# Main.net
KiCad netlist of a schematic drawn in Altium Designer
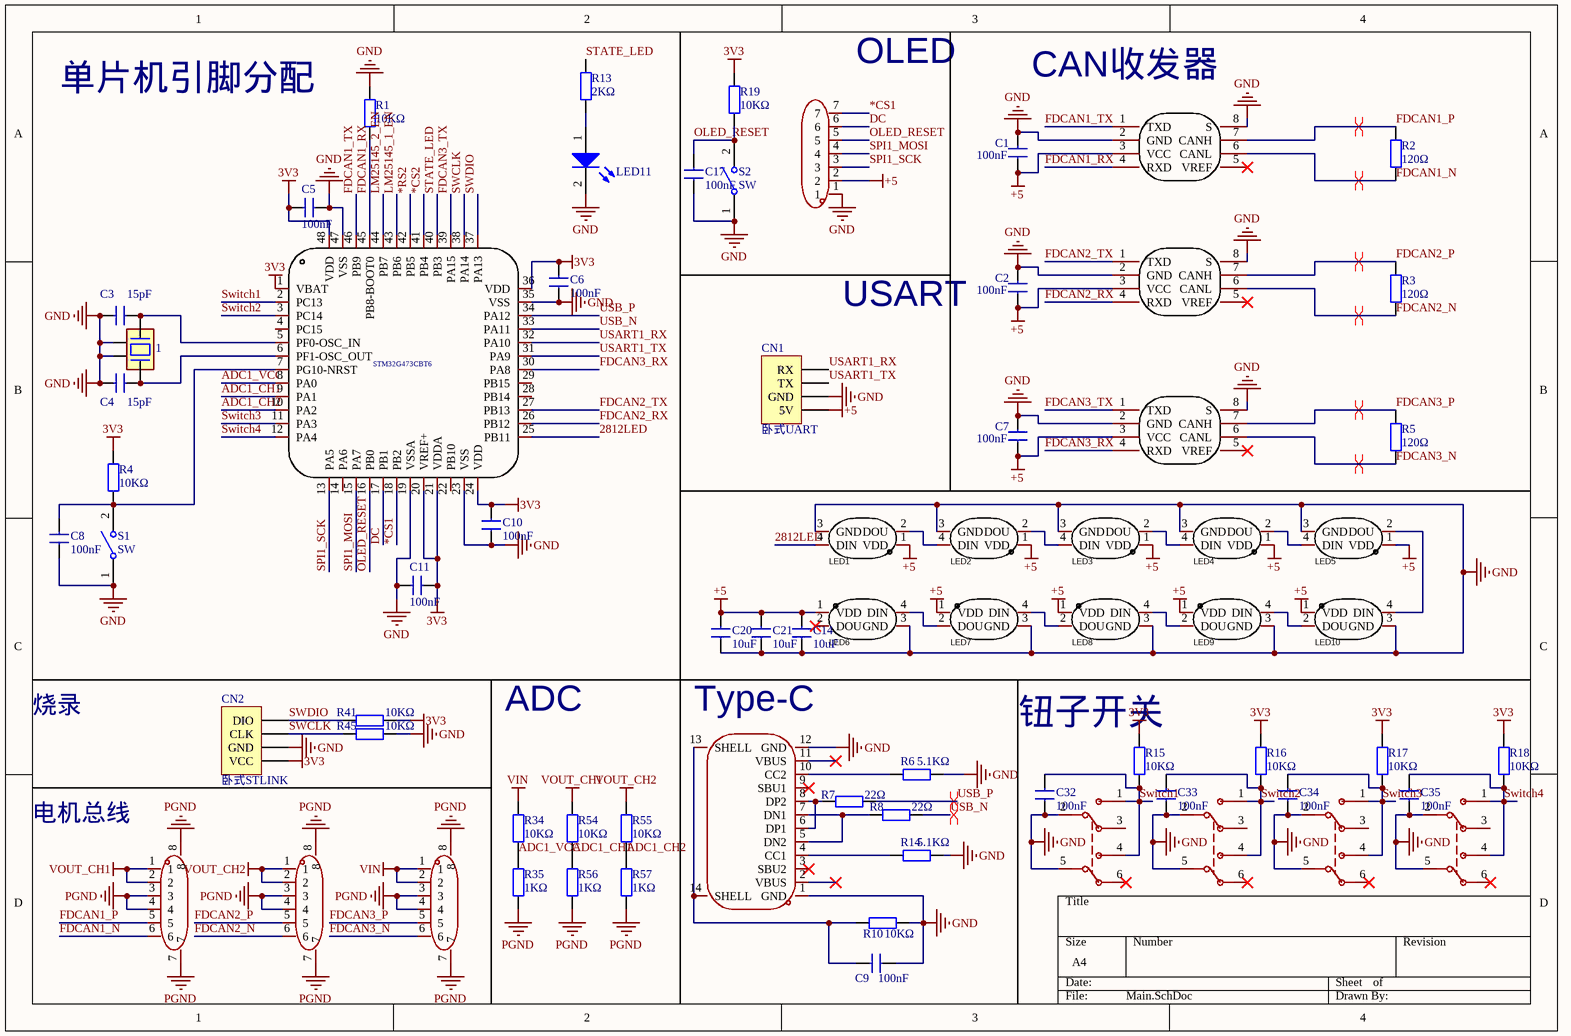
[diagram p0: Main.SchDoc]

(export (version "E")
  (design (tool "Eeschema 10.0.6"))
  (components
    (comp (ref "1")
      (value "3225贴片晶振")
      (footprint "OSC-3225-4P")
      (libsource (lib "Integrated_Library1") (part "3225贴片晶振"))
    )
    (comp (ref "C1")
      (value "100nF")
      (footprint "c0402")
      (description "贴片电容0402")
      (libsource (lib "Integrated_Library1") (part "0402贴片电容"))
    )
    (comp (ref "C2")
      (value "100nF")
      (footprint "c0402")
      (description "贴片电容0402")
      (libsource (lib "Integrated_Library1") (part "0402贴片电容"))
    )
    (comp (ref "C3")
      (value "15pF")
      (footprint "c0402")
      (description "贴片电容0402")
      (libsource (lib "Integrated_Library1") (part "0402贴片电容"))
    )
    (comp (ref "C4")
      (value "15pF")
      (footprint "c0402")
      (description "贴片电容0402")
      (libsource (lib "Integrated_Library1") (part "0402贴片电容"))
    )
    (comp (ref "C5")
      (value "100nF")
      (footprint "c0402")
      (description "贴片电容0402")
      (libsource (lib "Integrated_Library1") (part "0402贴片电容"))
    )
    (comp (ref "C6")
      (value "100nF")
      (footprint "c0402")
      (description "贴片电容0402")
      (libsource (lib "Integrated_Library1") (part "0402贴片电容"))
    )
    (comp (ref "C7")
      (value "100nF")
      (footprint "c0402")
      (description "贴片电容0402")
      (libsource (lib "Integrated_Library1") (part "0402贴片电容"))
    )
    (comp (ref "C8")
      (value "100nF")
      (footprint "c0402")
      (description "贴片电容0402")
      (libsource (lib "Integrated_Library1") (part "0402贴片电容"))
    )
    (comp (ref "C9")
      (value "100nF")
      (footprint "c0402")
      (description "贴片电容0402")
      (libsource (lib "Integrated_Library1") (part "0402贴片电容"))
    )
    (comp (ref "C10")
      (value "100nF")
      (footprint "c0402")
      (description "贴片电容0402")
      (libsource (lib "Integrated_Library1") (part "0402贴片电容"))
    )
    (comp (ref "C11")
      (value "100nF")
      (footprint "c0402")
      (description "贴片电容0402")
      (libsource (lib "Integrated_Library1") (part "0402贴片电容"))
    )
    (comp (ref "C14")
      (value "10uF")
      (footprint "1210")
      (description "1210贴片电容")
      (libsource (lib "Integrated_Library1") (part "1210贴片电容"))
    )
    (comp (ref "C17")
      (value "100nF")
      (footprint "c0402")
      (description "贴片电容0402")
      (libsource (lib "Integrated_Library1") (part "0402贴片电容"))
    )
    (comp (ref "C20")
      (value "10uF")
      (footprint "1210")
      (description "1210贴片电容")
      (libsource (lib "Integrated_Library1") (part "1210贴片电容"))
    )
    (comp (ref "C21")
      (value "10uF")
      (footprint "1210")
      (description "1210贴片电容")
      (libsource (lib "Integrated_Library1") (part "1210贴片电容"))
    )
    (comp (ref "C32")
      (value "100nF")
      (footprint "c0402")
      (description "贴片电容0402")
      (libsource (lib "Integrated_Library1") (part "0402贴片电容"))
    )
    (comp (ref "C33")
      (value "100nF")
      (footprint "c0402")
      (description "贴片电容0402")
      (libsource (lib "Integrated_Library1") (part "0402贴片电容"))
    )
    (comp (ref "C34")
      (value "100nF")
      (footprint "c0402")
      (description "贴片电容0402")
      (libsource (lib "Integrated_Library1") (part "0402贴片电容"))
    )
    (comp (ref "C35")
      (value "100nF")
      (footprint "c0402")
      (description "贴片电容0402")
      (libsource (lib "Integrated_Library1") (part "0402贴片电容"))
    )
    (comp (ref "CN1")
      (value "卧式UART")
      (footprint "CONN-SMD_4P-P1.25_GH1.25-4P")
      (libsource (lib "Integrated_Library1") (part "卧式UART"))
    )
    (comp (ref "CN2")
      (value "卧式STLINK")
      (footprint "CONN-SMD_4P-P1.25_GH1.25-4P")
      (libsource (lib "Integrated_Library1") (part "卧式STLINK"))
    )
    (comp (ref "H1")
      (value "PM254V-11-07-H85")
      (footprint "HDR-TH_7P-P2.54-V-F")
      (fields (field (name "MANUFACTURER") "XFCN(兴飞)"))
      (libsource (lib "Schlib1") (part "PM254V-11-07-H85"))
    )
    (comp (ref "LED1")
      (value "XL-5050RGBC-WS2812B")
      (footprint "LED-SMD_4P-L5.0-W5.0-BL_XL-5050RGBC")
      (description "WS2812B彩灯珠")
      (fields (field (name "MANUFACTURER") "XINGLIGHT(成兴光)"))
      (libsource (lib "RoBoMaster_AllComponent") (part "WS2812B彩灯珠"))
    )
    (comp (ref "LED2")
      (value "XL-5050RGBC-WS2812B")
      (footprint "LED-SMD_4P-L5.0-W5.0-BL_XL-5050RGBC")
      (description "WS2812B彩灯珠")
      (fields (field (name "MANUFACTURER") "XINGLIGHT(成兴光)"))
      (libsource (lib "RoBoMaster_AllComponent") (part "WS2812B彩灯珠"))
    )
    (comp (ref "LED3")
      (value "XL-5050RGBC-WS2812B")
      (footprint "LED-SMD_4P-L5.0-W5.0-BL_XL-5050RGBC")
      (description "WS2812B彩灯珠")
      (fields (field (name "MANUFACTURER") "XINGLIGHT(成兴光)"))
      (libsource (lib "RoBoMaster_AllComponent") (part "WS2812B彩灯珠"))
    )
    (comp (ref "LED4")
      (value "XL-5050RGBC-WS2812B")
      (footprint "LED-SMD_4P-L5.0-W5.0-BL_XL-5050RGBC")
      (description "WS2812B彩灯珠")
      (fields (field (name "MANUFACTURER") "XINGLIGHT(成兴光)"))
      (libsource (lib "RoBoMaster_AllComponent") (part "WS2812B彩灯珠"))
    )
    (comp (ref "LED5")
      (value "XL-5050RGBC-WS2812B")
      (footprint "LED-SMD_4P-L5.0-W5.0-BL_XL-5050RGBC")
      (description "WS2812B彩灯珠")
      (fields (field (name "MANUFACTURER") "XINGLIGHT(成兴光)"))
      (libsource (lib "RoBoMaster_AllComponent") (part "WS2812B彩灯珠"))
    )
    (comp (ref "LED6")
      (value "XL-5050RGBC-WS2812B")
      (footprint "LED-SMD_4P-L5.0-W5.0-BL_XL-5050RGBC")
      (description "WS2812B彩灯珠")
      (fields (field (name "MANUFACTURER") "XINGLIGHT(成兴光)"))
      (libsource (lib "RoBoMaster_AllComponent") (part "WS2812B彩灯珠"))
    )
    (comp (ref "LED7")
      (value "XL-5050RGBC-WS2812B")
      (footprint "LED-SMD_4P-L5.0-W5.0-BL_XL-5050RGBC")
      (description "WS2812B彩灯珠")
      (fields (field (name "MANUFACTURER") "XINGLIGHT(成兴光)"))
      (libsource (lib "RoBoMaster_AllComponent") (part "WS2812B彩灯珠"))
    )
    (comp (ref "LED8")
      (value "XL-5050RGBC-WS2812B")
      (footprint "LED-SMD_4P-L5.0-W5.0-BL_XL-5050RGBC")
      (description "WS2812B彩灯珠")
      (fields (field (name "MANUFACTURER") "XINGLIGHT(成兴光)"))
      (libsource (lib "RoBoMaster_AllComponent") (part "WS2812B彩灯珠"))
    )
    (comp (ref "LED9")
      (value "XL-5050RGBC-WS2812B")
      (footprint "LED-SMD_4P-L5.0-W5.0-BL_XL-5050RGBC")
      (description "WS2812B彩灯珠")
      (fields (field (name "MANUFACTURER") "XINGLIGHT(成兴光)"))
      (libsource (lib "RoBoMaster_AllComponent") (part "WS2812B彩灯珠"))
    )
    (comp (ref "LED10")
      (value "XL-5050RGBC-WS2812B")
      (footprint "LED-SMD_4P-L5.0-W5.0-BL_XL-5050RGBC")
      (description "WS2812B彩灯珠")
      (fields (field (name "MANUFACTURER") "XINGLIGHT(成兴光)"))
      (libsource (lib "RoBoMaster_AllComponent") (part "WS2812B彩灯珠"))
    )
    (comp (ref "LED11")
      (value "LED")
      (footprint "led0805")
      (description "0805贴片LED")
      (libsource (lib "Integrated_Library1") (part "0805贴片LED"))
    )
    (comp (ref "R1")
      (value "10KΩ")
      (footprint "R0402")
      (description "0402贴片电阻")
      (libsource (lib "") (part "0402贴片电阻_4"))
    )
    (comp (ref "R2")
      (value "120Ω")
      (footprint "R0402")
      (description "0402贴片电阻")
      (libsource (lib "Integrated_Library1") (part "0402贴片电阻"))
    )
    (comp (ref "R3")
      (value "120Ω")
      (footprint "R0402")
      (description "0402贴片电阻")
      (libsource (lib "Integrated_Library1") (part "0402贴片电阻"))
    )
    (comp (ref "R4")
      (value "10KΩ")
      (footprint "R0402")
      (description "0402贴片电阻")
      (libsource (lib "Integrated_Library1") (part "0402贴片电阻"))
    )
    (comp (ref "R5")
      (value "120Ω")
      (footprint "R0402")
      (description "0402贴片电阻")
      (libsource (lib "Integrated_Library1") (part "0402贴片电阻"))
    )
    (comp (ref "R6")
      (value "5.1KΩ")
      (footprint "R0402")
      (description "0402贴片电阻")
      (libsource (lib "") (part "0402贴片电阻_1"))
    )
    (comp (ref "R7")
      (value "22Ω")
      (footprint "R0402")
      (description "0402贴片电阻")
      (libsource (lib "") (part "0402贴片电阻_1"))
    )
    (comp (ref "R8")
      (value "22Ω")
      (footprint "R0402")
      (description "0402贴片电阻")
      (libsource (lib "") (part "0402贴片电阻_1"))
    )
    (comp (ref "R10")
      (value "10KΩ")
      (footprint "R0402")
      (description "0402贴片电阻")
      (libsource (lib "") (part "0402贴片电阻_1"))
    )
    (comp (ref "R13")
      (value "2KΩ")
      (footprint "R0402")
      (description "0402贴片电阻")
      (libsource (lib "") (part "0402贴片电阻_3"))
    )
    (comp (ref "R14")
      (value "5.1KΩ")
      (footprint "R0402")
      (description "0402贴片电阻")
      (libsource (lib "") (part "0402贴片电阻_1"))
    )
    (comp (ref "R15")
      (value "10KΩ")
      (footprint "R0402")
      (description "0402贴片电阻")
      (libsource (lib "Integrated_Library1") (part "0402贴片电阻"))
    )
    (comp (ref "R16")
      (value "10KΩ")
      (footprint "R0402")
      (description "0402贴片电阻")
      (libsource (lib "Integrated_Library1") (part "0402贴片电阻"))
    )
    (comp (ref "R17")
      (value "10KΩ")
      (footprint "R0402")
      (description "0402贴片电阻")
      (libsource (lib "Integrated_Library1") (part "0402贴片电阻"))
    )
    (comp (ref "R18")
      (value "10KΩ")
      (footprint "R0402")
      (description "0402贴片电阻")
      (libsource (lib "Integrated_Library1") (part "0402贴片电阻"))
    )
    (comp (ref "R19")
      (value "10KΩ")
      (footprint "R0402")
      (description "0402贴片电阻")
      (libsource (lib "Integrated_Library1") (part "0402贴片电阻"))
    )
    (comp (ref "R34")
      (value "10KΩ")
      (footprint "R0402")
      (description "0402贴片电阻")
      (libsource (lib "") (part "0402贴片电阻_2"))
    )
    (comp (ref "R35")
      (value "1KΩ")
      (footprint "R0402")
      (description "0402贴片电阻")
      (libsource (lib "") (part "0402贴片电阻_2"))
    )
    (comp (ref "R41")
      (value "10KΩ")
      (footprint "R0402")
      (description "0402贴片电阻")
      (libsource (lib "") (part "0402贴片电阻_1"))
    )
    (comp (ref "R45")
      (value "10KΩ")
      (footprint "R0402")
      (description "0402贴片电阻")
      (libsource (lib "") (part "0402贴片电阻_1"))
    )
    (comp (ref "R54")
      (value "10KΩ")
      (footprint "R0402")
      (description "0402贴片电阻")
      (libsource (lib "") (part "0402贴片电阻_2"))
    )
    (comp (ref "R55")
      (value "10KΩ")
      (footprint "R0402")
      (description "0402贴片电阻")
      (libsource (lib "") (part "0402贴片电阻_2"))
    )
    (comp (ref "R56")
      (value "1KΩ")
      (footprint "R0402")
      (description "0402贴片电阻")
      (libsource (lib "") (part "0402贴片电阻_2"))
    )
    (comp (ref "R57")
      (value "1KΩ")
      (footprint "R0402")
      (description "0402贴片电阻")
      (libsource (lib "") (part "0402贴片电阻_2"))
    )
    (comp (ref "S1")
      (value "SW")
      (footprint "KEY_SMD")
      (description "开关")
      (libsource (lib "Integrated_Library1") (part "SW"))
    )
    (comp (ref "S2")
      (value "SW")
      (footprint "KEY_SMD")
      (description "开关")
      (libsource (lib "Integrated_Library1") (part "SW"))
    )
    (comp (ref "U1")
      (value "ZX-ZH1.5-6PWT")
      (footprint "CONN-SMD_6P-P1.50_ZX-ZH1.5-6PWT")
      (fields (field (name "MANUFACTURER") "Megastar(兆星)"))
      (libsource (lib "Schlib1") (part "ZX-ZH1.5-6PWT"))
    )
    (comp (ref "U2")
      (value "SN65HVD1050DR")
      (footprint "SOIC-8_L4.9-W3.9-P1.27-LS6.0-BL")
      (description "CAN芯片")
      (fields (field (name "MANUFACTURER") "TI(德州仪器)"))
      (libsource (lib "Integrated_Library1") (part "SN65HVD1050DR"))
    )
    (comp (ref "U3")
      (value "ZX-ZH1.5-6PWT")
      (footprint "CONN-SMD_6P-P1.50_ZX-ZH1.5-6PWT")
      (fields (field (name "MANUFACTURER") "Megastar(兆星)"))
      (libsource (lib "Schlib1") (part "ZX-ZH1.5-6PWT"))
    )
    (comp (ref "U4")
      (value "STM32G474CET6")
      (footprint "LQFP-48")
      (fields (field (name "MANUFACTURER") "ST(意法半导体)") (field (name "MANUFACTURER PART") "STM32G473CBT6"))
      (libsource (lib "Integrated_Library1") (part "STM32G474CET6"))
    )
    (comp (ref "U5")
      (value "SN65HVD1050DR")
      (footprint "SOIC-8_L4.9-W3.9-P1.27-LS6.0-BL")
      (description "CAN芯片")
      (fields (field (name "MANUFACTURER") "TI(德州仪器)"))
      (libsource (lib "Integrated_Library1") (part "SN65HVD1050DR"))
    )
    (comp (ref "U6")
      (value "ZX-ZH1.5-6PWT")
      (footprint "CONN-SMD_6P-P1.50_ZX-ZH1.5-6PWT")
      (fields (field (name "MANUFACTURER") "Megastar(兆星)"))
      (libsource (lib "Schlib1") (part "ZX-ZH1.5-6PWT"))
    )
    (comp (ref "U8")
      (value "SN65HVD1050DR")
      (footprint "SOIC-8_L4.9-W3.9-P1.27-LS6.0-BL")
      (description "CAN芯片")
      (fields (field (name "MANUFACTURER") "TI(德州仪器)"))
      (libsource (lib "Integrated_Library1") (part "SN65HVD1050DR"))
    )
    (comp (ref "U9")
      (value "7208P1YZQI")
      (footprint "SW-TH_6P-L12.7-W11.4-P4.70-LS4.8")
      (fields (field (name "MANUFACTURER") "C&K"))
      (libsource (lib "Schlib1") (part "7208P1YZQI"))
    )
    (comp (ref "U10")
      (value "7208P1YZQI")
      (footprint "SW-TH_6P-L12.7-W11.4-P4.70-LS4.8")
      (fields (field (name "MANUFACTURER") "C&K"))
      (libsource (lib "Schlib1") (part "7208P1YZQI"))
    )
    (comp (ref "U11")
      (value "7208P1YZQI")
      (footprint "SW-TH_6P-L12.7-W11.4-P4.70-LS4.8")
      (fields (field (name "MANUFACTURER") "C&K"))
      (libsource (lib "Schlib1") (part "7208P1YZQI"))
    )
    (comp (ref "U12")
      (value "7208P1YZQI")
      (footprint "SW-TH_6P-L12.7-W11.4-P4.70-LS4.8")
      (fields (field (name "MANUFACTURER") "C&K"))
      (libsource (lib "Schlib1") (part "7208P1YZQI"))
    )
    (comp (ref "USB1")
      (value "TYPE-C 16PIN 2MD(073)")
      (footprint "USB-C-SMD_TYPE-C-6PIN-2MD-073")
      (fields (field (name "MANUFACTURER") "SHOU HAN(首韩)"))
      (libsource (lib "Schlib1") (part "TYPE-C 16PIN 2MD(073)"))
    )
  )
  (nets
    (net (code "1") (name "+5") (class "Default")
      (node (ref "C1") (pin "1") (pinfunction "1_1") (pintype "passive"))
      (node (ref "C14") (pin "2") (pinfunction "2_2") (pintype "passive"))
      (node (ref "C2") (pin "1") (pinfunction "1_1") (pintype "passive"))
      (node (ref "C20") (pin "2") (pinfunction "2_2") (pintype "passive"))
      (node (ref "C21") (pin "2") (pinfunction "2_2") (pintype "passive"))
      (node (ref "C7") (pin "1") (pinfunction "1_1") (pintype "passive"))
      (node (ref "CN1") (pin "1") (pinfunction "5V_1") (pintype "passive"))
      (node (ref "H1") (pin "2") (pinfunction "2_2") (pintype "passive"))
      (node (ref "LED1") (pin "1") (pinfunction "VDD_1") (pintype "passive"))
      (node (ref "LED10") (pin "1") (pinfunction "VDD_1") (pintype "passive"))
      (node (ref "LED2") (pin "1") (pinfunction "VDD_1") (pintype "passive"))
      (node (ref "LED3") (pin "1") (pinfunction "VDD_1") (pintype "passive"))
      (node (ref "LED4") (pin "1") (pinfunction "VDD_1") (pintype "passive"))
      (node (ref "LED5") (pin "1") (pinfunction "VDD_1") (pintype "passive"))
      (node (ref "LED6") (pin "1") (pinfunction "VDD_1") (pintype "passive"))
      (node (ref "LED7") (pin "1") (pinfunction "VDD_1") (pintype "passive"))
      (node (ref "LED8") (pin "1") (pinfunction "VDD_1") (pintype "passive"))
      (node (ref "LED9") (pin "1") (pinfunction "VDD_1") (pintype "passive"))
      (node (ref "U2") (pin "3") (pinfunction "VCC_3") (pintype "passive"))
      (node (ref "U5") (pin "3") (pinfunction "VCC_3") (pintype "passive"))
      (node (ref "U8") (pin "3") (pinfunction "VCC_3") (pintype "passive"))
    )
    (net (code "2") (name "/*CS1") (class "Default")
      (node (ref "H1") (pin "7") (pinfunction "7_7") (pintype "passive"))
      (node (ref "U4") (pin "18") (pinfunction "PB2_18") (pintype "passive"))
    )
    (net (code "3") (name "/*CS2") (class "Default")
      (node (ref "U4") (pin "41") (pinfunction "PB4_41") (pintype "passive"))
    )
    (net (code "4") (name "/*RS2") (class "Default")
      (node (ref "U4") (pin "42") (pinfunction "PB5_42") (pintype "passive"))
    )
    (net (code "5") (name "/2812LED") (class "Default")
      (node (ref "LED1") (pin "4") (pinfunction "DIN_4") (pintype "passive"))
      (node (ref "U4") (pin "25") (pinfunction "PB11_25") (pintype "passive"))
    )
    (net (code "6") (name "/ADC1_CH1") (class "Default")
      (node (ref "R54") (pin "1") (pinfunction "1_1") (pintype "passive"))
      (node (ref "R56") (pin "2") (pinfunction "2_2") (pintype "passive"))
      (node (ref "U4") (pin "9") (pinfunction "PA1_9") (pintype "passive"))
    )
    (net (code "7") (name "/ADC1_CH2") (class "Default")
      (node (ref "R55") (pin "1") (pinfunction "1_1") (pintype "passive"))
      (node (ref "R57") (pin "2") (pinfunction "2_2") (pintype "passive"))
      (node (ref "U4") (pin "10") (pinfunction "PA2_10") (pintype "passive"))
    )
    (net (code "8") (name "/ADC1_VCC") (class "Default")
      (node (ref "R34") (pin "1") (pinfunction "1_1") (pintype "passive"))
      (node (ref "R35") (pin "2") (pinfunction "2_2") (pintype "passive"))
      (node (ref "U4") (pin "8") (pinfunction "PA0_8") (pintype "passive"))
    )
    (net (code "9") (name "/DC") (class "Default")
      (node (ref "H1") (pin "6") (pinfunction "6_6") (pintype "passive"))
      (node (ref "U4") (pin "17") (pinfunction "PB1_17") (pintype "passive"))
    )
    (net (code "10") (name "/FDCAN1_N") (class "Default")
      (node (ref "R2") (pin "1") (pinfunction "1_1") (pintype "passive"))
      (node (ref "U1") (pin "6") (pinfunction "6_6") (pintype "passive"))
      (node (ref "U2") (pin "6") (pinfunction "CANL_6") (pintype "passive"))
    )
    (net (code "11") (name "/FDCAN1_P") (class "Default")
      (node (ref "R2") (pin "2") (pinfunction "2_2") (pintype "passive"))
      (node (ref "U1") (pin "5") (pinfunction "5_5") (pintype "passive"))
      (node (ref "U2") (pin "7") (pinfunction "CANH_7") (pintype "passive"))
    )
    (net (code "12") (name "/FDCAN1_RX") (class "Default")
      (node (ref "R1") (pin "2") (pinfunction "2_2") (pintype "passive"))
      (node (ref "U2") (pin "4") (pinfunction "RXD_4") (pintype "passive"))
      (node (ref "U4") (pin "45") (pinfunction "PB8-BOOT0_45") (pintype "passive"))
    )
    (net (code "13") (name "/FDCAN1_TX") (class "Default")
      (node (ref "U2") (pin "1") (pinfunction "TXD_1") (pintype "passive"))
      (node (ref "U4") (pin "46") (pinfunction "PB9_46") (pintype "passive"))
    )
    (net (code "14") (name "/FDCAN2_N") (class "Default")
      (node (ref "R3") (pin "1") (pinfunction "1_1") (pintype "passive"))
      (node (ref "U3") (pin "6") (pinfunction "6_6") (pintype "passive"))
      (node (ref "U5") (pin "6") (pinfunction "CANL_6") (pintype "passive"))
    )
    (net (code "15") (name "/FDCAN2_P") (class "Default")
      (node (ref "R3") (pin "2") (pinfunction "2_2") (pintype "passive"))
      (node (ref "U3") (pin "5") (pinfunction "5_5") (pintype "passive"))
      (node (ref "U5") (pin "7") (pinfunction "CANH_7") (pintype "passive"))
    )
    (net (code "16") (name "/FDCAN2_RX") (class "Default")
      (node (ref "U4") (pin "26") (pinfunction "PB12_26") (pintype "passive"))
      (node (ref "U5") (pin "4") (pinfunction "RXD_4") (pintype "passive"))
    )
    (net (code "17") (name "/FDCAN2_TX") (class "Default")
      (node (ref "U4") (pin "27") (pinfunction "PB13_27") (pintype "passive"))
      (node (ref "U5") (pin "1") (pinfunction "TXD_1") (pintype "passive"))
    )
    (net (code "18") (name "/FDCAN3_N") (class "Default")
      (node (ref "R5") (pin "1") (pinfunction "1_1") (pintype "passive"))
      (node (ref "U6") (pin "6") (pinfunction "6_6") (pintype "passive"))
      (node (ref "U8") (pin "6") (pinfunction "CANL_6") (pintype "passive"))
    )
    (net (code "19") (name "/FDCAN3_P") (class "Default")
      (node (ref "R5") (pin "2") (pinfunction "2_2") (pintype "passive"))
      (node (ref "U6") (pin "5") (pinfunction "5_5") (pintype "passive"))
      (node (ref "U8") (pin "7") (pinfunction "CANH_7") (pintype "passive"))
    )
    (net (code "20") (name "/FDCAN3_RX") (class "Default")
      (node (ref "U4") (pin "30") (pinfunction "PA8_30") (pintype "passive"))
      (node (ref "U8") (pin "4") (pinfunction "RXD_4") (pintype "passive"))
    )
    (net (code "21") (name "/FDCAN3_TX") (class "Default")
      (node (ref "U4") (pin "39") (pinfunction "PA15_39") (pintype "passive"))
      (node (ref "U8") (pin "1") (pinfunction "TXD_1") (pintype "passive"))
    )
    (net (code "22") (name "/LM25145_1_EN") (class "Default")
      (node (ref "U4") (pin "43") (pinfunction "PB6_43") (pintype "passive"))
    )
    (net (code "23") (name "/LM25145_2_EN") (class "Default")
      (node (ref "U4") (pin "44") (pinfunction "PB7_44") (pintype "passive"))
    )
    (net (code "24") (name "/OLED_RESET") (class "Default")
      (node (ref "C17") (pin "2") (pinfunction "2_2") (pintype "passive"))
      (node (ref "H1") (pin "5") (pinfunction "5_5") (pintype "passive"))
      (node (ref "R19") (pin "1") (pinfunction "1_1") (pintype "passive"))
      (node (ref "S2") (pin "2") (pinfunction "NO_2") (pintype "passive"))
      (node (ref "U4") (pin "16") (pinfunction "PB0_16") (pintype "passive"))
    )
    (net (code "25") (name "/SPI1_MOSI") (class "Default")
      (node (ref "H1") (pin "4") (pinfunction "4_4") (pintype "passive"))
      (node (ref "U4") (pin "15") (pinfunction "PA7_15") (pintype "passive"))
    )
    (net (code "26") (name "/SPI1_SCK") (class "Default")
      (node (ref "H1") (pin "3") (pinfunction "3_3") (pintype "passive"))
      (node (ref "U4") (pin "13") (pinfunction "PA5_13") (pintype "passive"))
    )
    (net (code "27") (name "/STATE_LED") (class "Default")
      (node (ref "R13") (pin "1") (pinfunction "1_1") (pintype "passive"))
      (node (ref "U4") (pin "40") (pinfunction "PB3_40") (pintype "passive"))
    )
    (net (code "28") (name "/SWCLK") (class "Default")
      (node (ref "CN2") (pin "3") (pinfunction "CLK_3") (pintype "passive"))
      (node (ref "R45") (pin "1") (pinfunction "1_1") (pintype "passive"))
      (node (ref "U4") (pin "38") (pinfunction "PA14_38") (pintype "passive"))
    )
    (net (code "29") (name "/SWDIO") (class "Default")
      (node (ref "CN2") (pin "4") (pinfunction "DIO_4") (pintype "passive"))
      (node (ref "R41") (pin "1") (pinfunction "1_1") (pintype "passive"))
      (node (ref "U4") (pin "37") (pinfunction "PA13_37") (pintype "passive"))
    )
    (net (code "30") (name "/Switch1") (class "Default")
      (node (ref "C32") (pin "2") (pinfunction "2_2") (pintype "passive"))
      (node (ref "R15") (pin "1") (pinfunction "1_1") (pintype "passive"))
      (node (ref "U4") (pin "2") (pinfunction "PC13_2") (pintype "passive"))
      (node (ref "U9") (pin "1") (pinfunction "1_1") (pintype "passive"))
      (node (ref "U9") (pin "4") (pinfunction "4_4") (pintype "passive"))
    )
    (net (code "31") (name "/Switch2") (class "Default")
      (node (ref "C33") (pin "2") (pinfunction "2_2") (pintype "passive"))
      (node (ref "R16") (pin "1") (pinfunction "1_1") (pintype "passive"))
      (node (ref "U10") (pin "1") (pinfunction "1_1") (pintype "passive"))
      (node (ref "U10") (pin "4") (pinfunction "4_4") (pintype "passive"))
      (node (ref "U4") (pin "3") (pinfunction "PC14_3") (pintype "passive"))
    )
    (net (code "32") (name "/Switch3") (class "Default")
      (node (ref "C34") (pin "2") (pinfunction "2_2") (pintype "passive"))
      (node (ref "R17") (pin "1") (pinfunction "1_1") (pintype "passive"))
      (node (ref "U11") (pin "1") (pinfunction "1_1") (pintype "passive"))
      (node (ref "U11") (pin "4") (pinfunction "4_4") (pintype "passive"))
      (node (ref "U4") (pin "11") (pinfunction "PA3_11") (pintype "passive"))
    )
    (net (code "33") (name "/Switch4") (class "Default")
      (node (ref "C35") (pin "2") (pinfunction "2_2") (pintype "passive"))
      (node (ref "R18") (pin "1") (pinfunction "1_1") (pintype "passive"))
      (node (ref "U12") (pin "1") (pinfunction "1_1") (pintype "passive"))
      (node (ref "U12") (pin "4") (pinfunction "4_4") (pintype "passive"))
      (node (ref "U4") (pin "12") (pinfunction "PA4_12") (pintype "passive"))
    )
    (net (code "34") (name "/USART1_RX") (class "Default")
      (node (ref "CN1") (pin "4") (pinfunction "RX_4") (pintype "passive"))
      (node (ref "U4") (pin "32") (pinfunction "PA10_32") (pintype "passive"))
    )
    (net (code "35") (name "/USART1_TX") (class "Default")
      (node (ref "CN1") (pin "3") (pinfunction "TX_3") (pintype "passive"))
      (node (ref "U4") (pin "31") (pinfunction "PA9_31") (pintype "passive"))
    )
    (net (code "36") (name "/USB_N") (class "Default")
      (node (ref "R8") (pin "2") (pinfunction "2_2") (pintype "passive"))
      (node (ref "U4") (pin "33") (pinfunction "PA11_33") (pintype "passive"))
    )
    (net (code "37") (name "/USB_P") (class "Default")
      (node (ref "R7") (pin "2") (pinfunction "2_2") (pintype "passive"))
      (node (ref "U4") (pin "34") (pinfunction "PA12_34") (pintype "passive"))
    )
    (net (code "38") (name "3V3") (class "Default")
      (node (ref "C10") (pin "2") (pinfunction "2_2") (pintype "passive"))
      (node (ref "C11") (pin "1") (pinfunction "1_1") (pintype "passive"))
      (node (ref "C5") (pin "2") (pinfunction "2_2") (pintype "passive"))
      (node (ref "C6") (pin "2") (pinfunction "2_2") (pintype "passive"))
      (node (ref "CN2") (pin "1") (pinfunction "VCC_1") (pintype "passive"))
      (node (ref "R15") (pin "2") (pinfunction "2_2") (pintype "passive"))
      (node (ref "R16") (pin "2") (pinfunction "2_2") (pintype "passive"))
      (node (ref "R17") (pin "2") (pinfunction "2_2") (pintype "passive"))
      (node (ref "R18") (pin "2") (pinfunction "2_2") (pintype "passive"))
      (node (ref "R19") (pin "2") (pinfunction "2_2") (pintype "passive"))
      (node (ref "R4") (pin "2") (pinfunction "2_2") (pintype "passive"))
      (node (ref "R41") (pin "2") (pinfunction "2_2") (pintype "passive"))
      (node (ref "U4") (pin "1") (pinfunction "VBAT_1") (pintype "passive"))
      (node (ref "U4") (pin "20") (pinfunction "VREF+_20") (pintype "passive"))
      (node (ref "U4") (pin "21") (pinfunction "VDDA_21") (pintype "passive"))
      (node (ref "U4") (pin "24") (pinfunction "VDD_24") (pintype "passive"))
      (node (ref "U4") (pin "36") (pinfunction "VDD_36") (pintype "passive"))
      (node (ref "U4") (pin "48") (pinfunction "VDD_48") (pintype "passive"))
    )
    (net (code "39") (name "GND") (class "Default")
      (node (ref "1") (pin "2") (pinfunction "2_2") (pintype "passive"))
      (node (ref "1") (pin "4") (pinfunction "4_4") (pintype "passive"))
      (node (ref "C1") (pin "2") (pinfunction "2_2") (pintype "passive"))
      (node (ref "C10") (pin "1") (pinfunction "1_1") (pintype "passive"))
      (node (ref "C11") (pin "2") (pinfunction "2_2") (pintype "passive"))
      (node (ref "C14") (pin "1") (pinfunction "1_1") (pintype "passive"))
      (node (ref "C17") (pin "1") (pinfunction "1_1") (pintype "passive"))
      (node (ref "C2") (pin "2") (pinfunction "2_2") (pintype "passive"))
      (node (ref "C20") (pin "1") (pinfunction "1_1") (pintype "passive"))
      (node (ref "C21") (pin "1") (pinfunction "1_1") (pintype "passive"))
      (node (ref "C3") (pin "1") (pinfunction "1_1") (pintype "passive"))
      (node (ref "C32") (pin "1") (pinfunction "1_1") (pintype "passive"))
      (node (ref "C33") (pin "1") (pinfunction "1_1") (pintype "passive"))
      (node (ref "C34") (pin "1") (pinfunction "1_1") (pintype "passive"))
      (node (ref "C35") (pin "1") (pinfunction "1_1") (pintype "passive"))
      (node (ref "C4") (pin "1") (pinfunction "1_1") (pintype "passive"))
      (node (ref "C5") (pin "1") (pinfunction "1_1") (pintype "passive"))
      (node (ref "C6") (pin "1") (pinfunction "1_1") (pintype "passive"))
      (node (ref "C7") (pin "2") (pinfunction "2_2") (pintype "passive"))
      (node (ref "C8") (pin "1") (pinfunction "1_1") (pintype "passive"))
      (node (ref "C9") (pin "2") (pinfunction "2_2") (pintype "passive"))
      (node (ref "CN1") (pin "2") (pinfunction "GND_2") (pintype "passive"))
      (node (ref "CN2") (pin "2") (pinfunction "GND_2") (pintype "passive"))
      (node (ref "H1") (pin "1") (pinfunction "1_1") (pintype "passive"))
      (node (ref "LED1") (pin "3") (pinfunction "GND_3") (pintype "passive"))
      (node (ref "LED10") (pin "3") (pinfunction "GND_3") (pintype "passive"))
      (node (ref "LED11") (pin "2") (pinfunction "K_2") (pintype "passive"))
      (node (ref "LED2") (pin "3") (pinfunction "GND_3") (pintype "passive"))
      (node (ref "LED3") (pin "3") (pinfunction "GND_3") (pintype "passive"))
      (node (ref "LED4") (pin "3") (pinfunction "GND_3") (pintype "passive"))
      (node (ref "LED5") (pin "3") (pinfunction "GND_3") (pintype "passive"))
      (node (ref "LED6") (pin "3") (pinfunction "GND_3") (pintype "passive"))
      (node (ref "LED7") (pin "3") (pinfunction "GND_3") (pintype "passive"))
      (node (ref "LED8") (pin "3") (pinfunction "GND_3") (pintype "passive"))
      (node (ref "LED9") (pin "3") (pinfunction "GND_3") (pintype "passive"))
      (node (ref "R1") (pin "1") (pinfunction "1_1") (pintype "passive"))
      (node (ref "R10") (pin "2") (pinfunction "2_2") (pintype "passive"))
      (node (ref "R14") (pin "2") (pinfunction "2_2") (pintype "passive"))
      (node (ref "R45") (pin "2") (pinfunction "2_2") (pintype "passive"))
      (node (ref "R6") (pin "2") (pinfunction "2_2") (pintype "passive"))
      (node (ref "S1") (pin "1") (pinfunction "COMMON_1") (pintype "passive"))
      (node (ref "S2") (pin "1") (pinfunction "COMMON_1") (pintype "passive"))
      (node (ref "U10") (pin "2") (pinfunction "2_2") (pintype "passive"))
      (node (ref "U10") (pin "5") (pinfunction "5_5") (pintype "passive"))
      (node (ref "U11") (pin "2") (pinfunction "2_2") (pintype "passive"))
      (node (ref "U11") (pin "5") (pinfunction "5_5") (pintype "passive"))
      (node (ref "U12") (pin "2") (pinfunction "2_2") (pintype "passive"))
      (node (ref "U12") (pin "5") (pinfunction "5_5") (pintype "passive"))
      (node (ref "U2") (pin "2") (pinfunction "GND_2") (pintype "passive"))
      (node (ref "U2") (pin "8") (pinfunction "S_8") (pintype "passive"))
      (node (ref "U4") (pin "19") (pinfunction "VSSA_19") (pintype "passive"))
      (node (ref "U4") (pin "23") (pinfunction "VSS_23") (pintype "passive"))
      (node (ref "U4") (pin "35") (pinfunction "VSS_35") (pintype "passive"))
      (node (ref "U4") (pin "47") (pinfunction "VSS_47") (pintype "passive"))
      (node (ref "U5") (pin "2") (pinfunction "GND_2") (pintype "passive"))
      (node (ref "U5") (pin "8") (pinfunction "S_8") (pintype "passive"))
      (node (ref "U8") (pin "2") (pinfunction "GND_2") (pintype "passive"))
      (node (ref "U8") (pin "8") (pinfunction "S_8") (pintype "passive"))
      (node (ref "U9") (pin "2") (pinfunction "2_2") (pintype "passive"))
      (node (ref "U9") (pin "5") (pinfunction "5_5") (pintype "passive"))
      (node (ref "USB1") (pin "1") (pinfunction "GND_1") (pintype "passive"))
      (node (ref "USB1") (pin "12") (pinfunction "GND_12") (pintype "passive"))
    )
    (net (code "40") (name "Net-(C9-Pad1)") (class "Default")
      (node (ref "C9") (pin "1") (pinfunction "1_1") (pintype "passive"))
      (node (ref "R10") (pin "1") (pinfunction "1_1") (pintype "passive"))
      (node (ref "USB1") (pin "13") (pinfunction "SHELL_13") (pintype "passive"))
      (node (ref "USB1") (pin "14") (pinfunction "SHELL_14") (pintype "passive"))
    )
    (net (code "41") (name "Net-(LED1-DOU)") (class "Default")
      (node (ref "LED1") (pin "2") (pinfunction "DOU_2") (pintype "passive"))
      (node (ref "LED2") (pin "4") (pinfunction "DIN_4") (pintype "passive"))
    )
    (net (code "42") (name "Net-(LED2-DOU)") (class "Default")
      (node (ref "LED2") (pin "2") (pinfunction "DOU_2") (pintype "passive"))
      (node (ref "LED3") (pin "4") (pinfunction "DIN_4") (pintype "passive"))
    )
    (net (code "43") (name "Net-(LED3-DOU)") (class "Default")
      (node (ref "LED3") (pin "2") (pinfunction "DOU_2") (pintype "passive"))
      (node (ref "LED4") (pin "4") (pinfunction "DIN_4") (pintype "passive"))
    )
    (net (code "44") (name "Net-(LED4-DOU)") (class "Default")
      (node (ref "LED4") (pin "2") (pinfunction "DOU_2") (pintype "passive"))
      (node (ref "LED5") (pin "4") (pinfunction "DIN_4") (pintype "passive"))
    )
    (net (code "45") (name "Net-(LED6-DIN)") (class "Default")
      (node (ref "LED6") (pin "4") (pinfunction "DIN_4") (pintype "passive"))
      (node (ref "LED7") (pin "2") (pinfunction "DOU_2") (pintype "passive"))
    )
    (net (code "46") (name "Net-(LED7-DIN)") (class "Default")
      (node (ref "LED7") (pin "4") (pinfunction "DIN_4") (pintype "passive"))
      (node (ref "LED8") (pin "2") (pinfunction "DOU_2") (pintype "passive"))
    )
    (net (code "47") (name "Net-(LED8-DIN)") (class "Default")
      (node (ref "LED8") (pin "4") (pinfunction "DIN_4") (pintype "passive"))
      (node (ref "LED9") (pin "2") (pinfunction "DOU_2") (pintype "passive"))
    )
    (net (code "48") (name "Net-(LED10-DIN)") (class "Default")
      (node (ref "LED10") (pin "4") (pinfunction "DIN_4") (pintype "passive"))
      (node (ref "LED5") (pin "2") (pinfunction "DOU_2") (pintype "passive"))
    )
    (net (code "49") (name "Net-(LED10-DOU)") (class "Default")
      (node (ref "LED10") (pin "2") (pinfunction "DOU_2") (pintype "passive"))
      (node (ref "LED9") (pin "4") (pinfunction "DIN_4") (pintype "passive"))
    )
    (net (code "50") (name "Net-(LED11-A)") (class "Default")
      (node (ref "LED11") (pin "1") (pinfunction "A_1") (pintype "passive"))
      (node (ref "R13") (pin "2") (pinfunction "2_2") (pintype "passive"))
    )
    (net (code "51") (name "Net-(S1-NO)") (class "Default")
      (node (ref "C8") (pin "2") (pinfunction "2_2") (pintype "passive"))
      (node (ref "R4") (pin "1") (pinfunction "1_1") (pintype "passive"))
      (node (ref "S1") (pin "2") (pinfunction "NO_2") (pintype "passive"))
      (node (ref "U4") (pin "7") (pinfunction "PG10-NRST_7") (pintype "passive"))
    )
    (net (code "52") (name "Net-(U4-PF0-OSC_IN)") (class "Default")
      (node (ref "1") (pin "3") (pinfunction "3_3") (pintype "passive"))
      (node (ref "C3") (pin "2") (pinfunction "2_2") (pintype "passive"))
      (node (ref "U4") (pin "5") (pinfunction "PF0-OSC_IN_5") (pintype "passive"))
    )
    (net (code "53") (name "Net-(U4-PF1-OSC_OUT)") (class "Default")
      (node (ref "1") (pin "1") (pinfunction "1_1") (pintype "passive"))
      (node (ref "C4") (pin "2") (pinfunction "2_2") (pintype "passive"))
      (node (ref "U4") (pin "6") (pinfunction "PF1-OSC_OUT_6") (pintype "passive"))
    )
    (net (code "54") (name "Net-(USB1-CC1)") (class "Default")
      (node (ref "R14") (pin "1") (pinfunction "1_1") (pintype "passive"))
      (node (ref "USB1") (pin "4") (pinfunction "CC1_4") (pintype "passive"))
    )
    (net (code "55") (name "Net-(USB1-CC2)") (class "Default")
      (node (ref "R6") (pin "1") (pinfunction "1_1") (pintype "passive"))
      (node (ref "USB1") (pin "10") (pinfunction "CC2_10") (pintype "passive"))
    )
    (net (code "56") (name "Net-(USB1-DN1)") (class "Default")
      (node (ref "R8") (pin "1") (pinfunction "1_1") (pintype "passive"))
      (node (ref "USB1") (pin "5") (pinfunction "DN2_5") (pintype "passive"))
      (node (ref "USB1") (pin "7") (pinfunction "DN1_7") (pintype "passive"))
    )
    (net (code "57") (name "Net-(USB1-DP1)") (class "Default")
      (node (ref "R7") (pin "1") (pinfunction "1_1") (pintype "passive"))
      (node (ref "USB1") (pin "6") (pinfunction "DP1_6") (pintype "passive"))
      (node (ref "USB1") (pin "8") (pinfunction "DP2_8") (pintype "passive"))
    )
    (net (code "58") (name "PGND") (class "Default")
      (node (ref "R35") (pin "1") (pinfunction "1_1") (pintype "passive"))
      (node (ref "R56") (pin "1") (pinfunction "1_1") (pintype "passive"))
      (node (ref "R57") (pin "1") (pinfunction "1_1") (pintype "passive"))
      (node (ref "U1") (pin "3") (pinfunction "3_3") (pintype "passive"))
      (node (ref "U1") (pin "4") (pinfunction "4_4") (pintype "passive"))
      (node (ref "U1") (pin "7") (pinfunction "7_7") (pintype "passive"))
      (node (ref "U1") (pin "8") (pinfunction "8_8") (pintype "passive"))
      (node (ref "U3") (pin "3") (pinfunction "3_3") (pintype "passive"))
      (node (ref "U3") (pin "4") (pinfunction "4_4") (pintype "passive"))
      (node (ref "U3") (pin "7") (pinfunction "7_7") (pintype "passive"))
      (node (ref "U3") (pin "8") (pinfunction "8_8") (pintype "passive"))
      (node (ref "U6") (pin "3") (pinfunction "3_3") (pintype "passive"))
      (node (ref "U6") (pin "4") (pinfunction "4_4") (pintype "passive"))
      (node (ref "U6") (pin "7") (pinfunction "7_7") (pintype "passive"))
      (node (ref "U6") (pin "8") (pinfunction "8_8") (pintype "passive"))
    )
    (net (code "59") (name "VIN") (class "Default")
      (node (ref "R34") (pin "2") (pinfunction "2_2") (pintype "passive"))
      (node (ref "U6") (pin "1") (pinfunction "1_1") (pintype "passive"))
      (node (ref "U6") (pin "2") (pinfunction "2_2") (pintype "passive"))
    )
    (net (code "60") (name "VOUT_CH1") (class "Default")
      (node (ref "R54") (pin "2") (pinfunction "2_2") (pintype "passive"))
      (node (ref "U1") (pin "1") (pinfunction "1_1") (pintype "passive"))
      (node (ref "U1") (pin "2") (pinfunction "2_2") (pintype "passive"))
    )
    (net (code "61") (name "VOUT_CH2") (class "Default")
      (node (ref "R55") (pin "2") (pinfunction "2_2") (pintype "passive"))
      (node (ref "U3") (pin "1") (pinfunction "1_1") (pintype "passive"))
      (node (ref "U3") (pin "2") (pinfunction "2_2") (pintype "passive"))
    )
    (net (code "62") (name "unconnected-(LED6-DOU-Pad2)") (class "Default")
      (node (ref "LED6") (pin "2") (pinfunction "DOU_2") (pintype "passive+no_connect"))
    )
    (net (code "63") (name "unconnected-(U2-VREF-Pad5)") (class "Default")
      (node (ref "U2") (pin "5") (pinfunction "VREF_5") (pintype "passive+no_connect"))
    )
    (net (code "64") (name "unconnected-(U4-PA6-Pad14)") (class "Default")
      (node (ref "U4") (pin "14") (pinfunction "PA6_14") (pintype "passive"))
    )
    (net (code "65") (name "unconnected-(U4-PB10-Pad22)") (class "Default")
      (node (ref "U4") (pin "22") (pinfunction "PB10_22") (pintype "passive"))
    )
    (net (code "66") (name "unconnected-(U4-PB14-Pad28)") (class "Default")
      (node (ref "U4") (pin "28") (pinfunction "PB14_28") (pintype "passive"))
    )
    (net (code "67") (name "unconnected-(U4-PB15-Pad29)") (class "Default")
      (node (ref "U4") (pin "29") (pinfunction "PB15_29") (pintype "passive"))
    )
    (net (code "68") (name "unconnected-(U4-PC15-Pad4)") (class "Default")
      (node (ref "U4") (pin "4") (pinfunction "PC15_4") (pintype "passive"))
    )
    (net (code "69") (name "unconnected-(U5-VREF-Pad5)") (class "Default")
      (node (ref "U5") (pin "5") (pinfunction "VREF_5") (pintype "passive+no_connect"))
    )
    (net (code "70") (name "unconnected-(U8-VREF-Pad5)") (class "Default")
      (node (ref "U8") (pin "5") (pinfunction "VREF_5") (pintype "passive+no_connect"))
    )
    (net (code "71") (name "unconnected-(U9-Pad3)") (class "Default")
      (node (ref "U9") (pin "3") (pinfunction "3_3") (pintype "passive"))
    )
    (net (code "72") (name "unconnected-(U9-Pad6)") (class "Default")
      (node (ref "U9") (pin "6") (pinfunction "6_6") (pintype "passive+no_connect"))
    )
    (net (code "73") (name "unconnected-(U10-Pad3)") (class "Default")
      (node (ref "U10") (pin "3") (pinfunction "3_3") (pintype "passive"))
    )
    (net (code "74") (name "unconnected-(U10-Pad6)") (class "Default")
      (node (ref "U10") (pin "6") (pinfunction "6_6") (pintype "passive+no_connect"))
    )
    (net (code "75") (name "unconnected-(U11-Pad3)") (class "Default")
      (node (ref "U11") (pin "3") (pinfunction "3_3") (pintype "passive"))
    )
    (net (code "76") (name "unconnected-(U11-Pad6)") (class "Default")
      (node (ref "U11") (pin "6") (pinfunction "6_6") (pintype "passive+no_connect"))
    )
    (net (code "77") (name "unconnected-(U12-Pad3)") (class "Default")
      (node (ref "U12") (pin "3") (pinfunction "3_3") (pintype "passive"))
    )
    (net (code "78") (name "unconnected-(U12-Pad6)") (class "Default")
      (node (ref "U12") (pin "6") (pinfunction "6_6") (pintype "passive+no_connect"))
    )
    (net (code "79") (name "unconnected-(USB1-SBU1-Pad9)") (class "Default")
      (node (ref "USB1") (pin "9") (pinfunction "SBU1_9") (pintype "passive+no_connect"))
    )
    (net (code "80") (name "unconnected-(USB1-SBU2-Pad3)") (class "Default")
      (node (ref "USB1") (pin "3") (pinfunction "SBU2_3") (pintype "passive+no_connect"))
    )
    (net (code "81") (name "unconnected-(USB1-VBUS-Pad2)") (class "Default")
      (node (ref "USB1") (pin "2") (pinfunction "VBUS_2") (pintype "passive+no_connect"))
    )
    (net (code "82") (name "unconnected-(USB1-VBUS-Pad11)") (class "Default")
      (node (ref "USB1") (pin "11") (pinfunction "VBUS_11") (pintype "passive+no_connect"))
    )
  )
)
